# IMD.net
KiCad netlist of a schematic drawn in Altium Designer
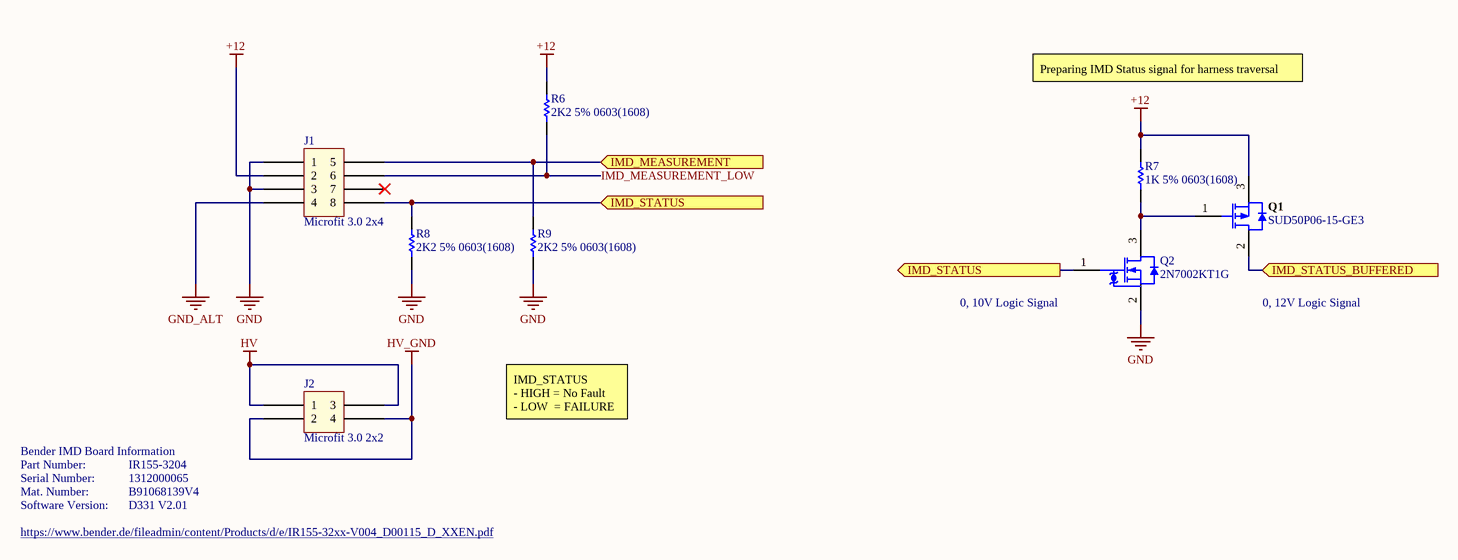
[diagram p0: IMD.SchDoc]

(export (version "E")
  (design (tool "Eeschema 10.0.6"))
  (components
    (comp (ref "J1")
      (value "Microfit 3.0 2x4")
      (footprint "Microfit_2X4_R_TH")
      (libsource (lib "QUTMS_Microfit") (part "Microfit_2x4"))
    )
    (comp (ref "J2")
      (value "Microfit 3.0 2x2")
      (footprint "Microfit_2X2_R_TH")
      (libsource (lib "QUTMS_Microfit") (part "Microfit_2x2"))
    )
    (comp (ref "Q1")
      (value "SUD50P06-15-GE3")
      (footprint "VSIL-TO-252AA-3_V")
      (description "P-Channel (D-S) MOSFET, 30 V, -55 to 150 degC, 3-Pin TO-252, RoHS, Tape and Reel")
      (fields (field (name "MANUFACTURER") "Vishay"))
      (libsource (lib "Altium Content Vault") (part "PEMOS-GDS-3"))
    )
    (comp (ref "Q2")
      (value "2N7002KT1G")
      (footprint "ONSC-SOT-23-3-318-08_V")
      (description "Small Signal MOSFET, 60 V, 380 mA, Single, N-Channel, 3-Pin SOT-23, Pb-Free, Tape and Reel")
      (fields (field (name "MANUFACTURER") "On Semiconductor"))
      (libsource (lib "Altium Content Vault") (part "ONSC-NMOS-G1S2D3-3_B"))
    )
    (comp (ref "R6")
      (value "2K2 5% 0603(1608)")
      (footprint "RESC0603(1608)_N")
      (description "2K2 0.1W 5% 0603 (1608 Metric)  SMD")
      (fields (field (name "POWER") "0.1 W") (field (name "TOLERANCE") "5 %"))
      (libsource (lib "Altium Content Vault") (part "RES"))
    )
    (comp (ref "R7")
      (value "1K 5% 0603(1608)")
      (footprint "RESC0603(1608)_L")
      (description "1K 0.1W 5% 0603 (1608 Metric)  SMD")
      (fields (field (name "TOLERANCE") "5 %") (field (name "POWER") "0.1 W"))
      (libsource (lib "Altium Content Vault") (part "RES"))
    )
    (comp (ref "R8")
      (value "2K2 5% 0603(1608)")
      (footprint "RESC0603(1608)_N")
      (description "2K2 0.1W 5% 0603 (1608 Metric)  SMD")
      (fields (field (name "POWER") "0.1 W") (field (name "TOLERANCE") "5 %"))
      (libsource (lib "Altium Content Vault") (part "RES"))
    )
    (comp (ref "R9")
      (value "2K2 5% 0603(1608)")
      (footprint "RESC0603(1608)_N")
      (description "2K2 0.1W 5% 0603 (1608 Metric)  SMD")
      (fields (field (name "POWER") "0.1 W") (field (name "TOLERANCE") "5 %"))
      (libsource (lib "Altium Content Vault") (part "RES"))
    )
  )
  (nets
    (net (code "1") (name "+12") (class "Default")
      (node (ref "J1") (pin "2") (pinfunction "2_2") (pintype "passive"))
      (node (ref "Q1") (pin "3") (pinfunction "S_3") (pintype "passive"))
      (node (ref "R6") (pin "2") (pinfunction "2_2") (pintype "passive"))
      (node (ref "R7") (pin "2") (pinfunction "2_2") (pintype "passive"))
    )
    (net (code "2") (name "/IMD_MEASUREMENT") (class "Default")
      (node (ref "J1") (pin "5") (pinfunction "5_5") (pintype "passive"))
      (node (ref "R9") (pin "2") (pinfunction "2_2") (pintype "passive"))
    )
    (net (code "3") (name "/IMD_MEASUREMENT_LOW") (class "Default")
      (node (ref "J1") (pin "6") (pinfunction "6_6") (pintype "passive"))
      (node (ref "R6") (pin "1") (pinfunction "1_1") (pintype "passive"))
    )
    (net (code "4") (name "/IMD_STATUS") (class "Default")
      (node (ref "J1") (pin "8") (pinfunction "8_8") (pintype "passive"))
      (node (ref "Q2") (pin "1") (pinfunction "G_1") (pintype "passive"))
      (node (ref "R8") (pin "2") (pinfunction "2_2") (pintype "passive"))
    )
    (net (code "5") (name "/IMD_STATUS_BUFFERED") (class "Default")
      (node (ref "Q1") (pin "2") (pinfunction "D_2") (pintype "passive"))
    )
    (net (code "6") (name "GND") (class "Default")
      (node (ref "J1") (pin "1") (pinfunction "1_1") (pintype "passive"))
      (node (ref "J1") (pin "3") (pinfunction "3_3") (pintype "passive"))
      (node (ref "Q2") (pin "2") (pinfunction "S_2") (pintype "passive"))
      (node (ref "R8") (pin "1") (pinfunction "1_1") (pintype "passive"))
      (node (ref "R9") (pin "1") (pinfunction "1_1") (pintype "passive"))
    )
    (net (code "7") (name "GND_ALT") (class "Default")
      (node (ref "J1") (pin "4") (pinfunction "4_4") (pintype "passive"))
    )
    (net (code "8") (name "HV") (class "Default")
      (node (ref "J2") (pin "1") (pinfunction "1_1") (pintype "passive"))
      (node (ref "J2") (pin "3") (pinfunction "3_3") (pintype "passive"))
    )
    (net (code "9") (name "HV_GND") (class "Default")
      (node (ref "J2") (pin "2") (pinfunction "2_2") (pintype "passive"))
      (node (ref "J2") (pin "4") (pinfunction "4_4") (pintype "passive"))
    )
    (net (code "10") (name "Net-(Q1-G)") (class "Default")
      (node (ref "Q1") (pin "1") (pinfunction "G_1") (pintype "passive"))
      (node (ref "Q2") (pin "3") (pinfunction "D_3") (pintype "passive"))
      (node (ref "R7") (pin "1") (pinfunction "1_1") (pintype "passive"))
    )
    (net (code "11") (name "unconnected-(J1-Pad7)") (class "Default")
      (node (ref "J1") (pin "7") (pinfunction "7_7") (pintype "passive+no_connect"))
    )
  )
)
